# circuitDiagram.net
KiCad netlist of a schematic drawn in EAGLE
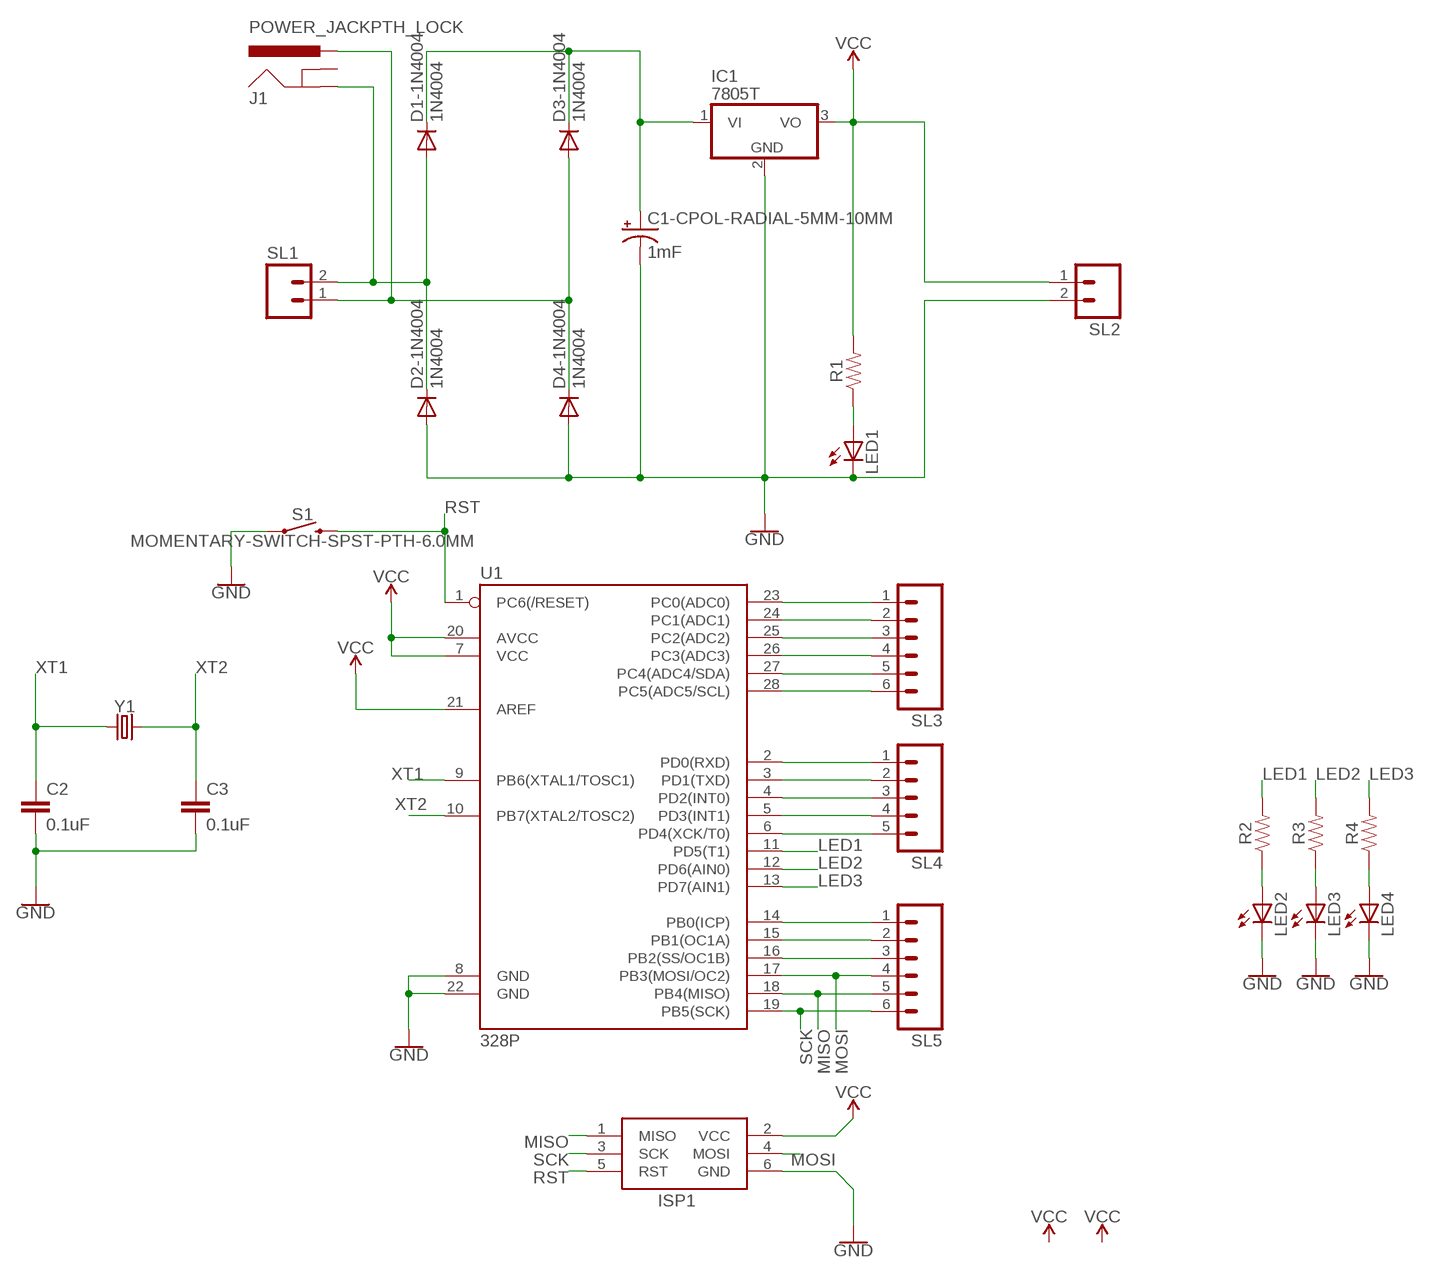
[diagram p0: schematic, sheet 1]

(export (version "E")
  (design (tool "Eeschema 10.0.6"))
  (components
    (comp (ref "C1-CPOL-RADIAL-5MM-10MM")
      (value "1mF")
      (footprint "eagle-import:CPOL-RADIAL-5MM-10MM")
      (libsource (lib "eagle-import") (part "1000UF-RADIAL-5MM-25V-20%"))
    )
    (comp (ref "C2")
      (value "0.1uF")
      (footprint "eagle-import:CAP-PTH-SMALL-KIT")
      (libsource (lib "eagle-import") (part "0.1UF-KIT-EZ-50V-20%"))
    )
    (comp (ref "C3")
      (value "0.1uF")
      (footprint "eagle-import:CAP-PTH-SMALL-KIT")
      (libsource (lib "eagle-import") (part "0.1UF-KIT-EZ-50V-20%"))
    )
    (comp (ref "D1-1N4004")
      (value "1N4004")
      (footprint "eagle-import:DO41-10")
      (libsource (lib "eagle-import") (part "1N4004"))
    )
    (comp (ref "D2-1N4004")
      (value "1N4004")
      (footprint "eagle-import:DO41-10")
      (libsource (lib "eagle-import") (part "1N4004"))
    )
    (comp (ref "D3-1N4004")
      (value "1N4004")
      (footprint "eagle-import:DO41-10")
      (libsource (lib "eagle-import") (part "1N4004"))
    )
    (comp (ref "D4-1N4004")
      (value "1N4004")
      (footprint "eagle-import:DO41-10")
      (libsource (lib "eagle-import") (part "1N4004"))
    )
    (comp (ref "IC1")
      (value "7805T")
      (footprint "eagle-import:TO220H")
      (libsource (lib "eagle-import") (part "78T05"))
    )
    (comp (ref "ISP1")
      (value "AVRISP-6")
      (footprint "eagle-import:AVRISP")
      (libsource (lib "eagle-import") (part "AVRISP-6"))
    )
    (comp (ref "J1")
      (value "POWER_JACKPTH_LOCK")
      (footprint "eagle-import:POWER_JACK_PTH_LOCK")
      (libsource (lib "eagle-import") (part "POWER_JACKPTH_LOCK"))
    )
    (comp (ref "LED1")
      (value "LED3MM")
      (footprint "eagle-import:LED3MM")
      (libsource (lib "eagle-import") (part "LED3MM"))
    )
    (comp (ref "LED2")
      (value "LED3MM")
      (footprint "eagle-import:LED3MM")
      (libsource (lib "eagle-import") (part "LED3MM"))
    )
    (comp (ref "LED3")
      (value "LED3MM")
      (footprint "eagle-import:LED3MM")
      (libsource (lib "eagle-import") (part "LED3MM"))
    )
    (comp (ref "LED4")
      (value "LED3MM")
      (footprint "eagle-import:LED3MM")
      (libsource (lib "eagle-import") (part "LED3MM"))
    )
    (comp (ref "R1")
      (value "RESISTORAXIAL-0.3")
      (footprint "eagle-import:AXIAL-0.3")
      (libsource (lib "eagle-import") (part "RESISTORAXIAL-0.3"))
    )
    (comp (ref "R2")
      (value "RESISTORAXIAL-0.3")
      (footprint "eagle-import:AXIAL-0.3")
      (libsource (lib "eagle-import") (part "RESISTORAXIAL-0.3"))
    )
    (comp (ref "R3")
      (value "RESISTORAXIAL-0.3")
      (footprint "eagle-import:AXIAL-0.3")
      (libsource (lib "eagle-import") (part "RESISTORAXIAL-0.3"))
    )
    (comp (ref "R4")
      (value "RESISTORAXIAL-0.3")
      (footprint "eagle-import:AXIAL-0.3")
      (libsource (lib "eagle-import") (part "RESISTORAXIAL-0.3"))
    )
    (comp (ref "S1")
      (value "MOMENTARY-SWITCH-SPST-PTH-6.0MM")
      (footprint "eagle-import:TACTILE_SWITCH_PTH_6.0MM")
      (libsource (lib "eagle-import") (part "MOMENTARY-SWITCH-SPST-PTH-6.0MM"))
    )
    (comp (ref "SL1")
      (value "M02")
      (footprint "eagle-import:02P")
      (libsource (lib "eagle-import") (part "M02"))
    )
    (comp (ref "SL2")
      (value "M02")
      (footprint "eagle-import:02P")
      (libsource (lib "eagle-import") (part "M02"))
    )
    (comp (ref "SL3")
      (value "M06")
      (footprint "eagle-import:06P")
      (libsource (lib "eagle-import") (part "M06"))
    )
    (comp (ref "SL4")
      (value "M05")
      (footprint "eagle-import:05P")
      (libsource (lib "eagle-import") (part "M05"))
    )
    (comp (ref "SL5")
      (value "M06")
      (footprint "eagle-import:06P")
      (libsource (lib "eagle-import") (part "M06"))
    )
    (comp (ref "U1")
      (value "328P")
      (footprint "eagle-import:DIP28")
      (libsource (lib "eagle-import") (part "ATMEGA328P_PDIP"))
    )
    (comp (ref "Y1")
      (value "CRYSTALPTH-HC49US")
      (footprint "eagle-import:HC49US")
      (libsource (lib "eagle-import") (part "CRYSTALPTH-HC49US"))
    )
  )
  (nets
    (net (code "1") (name "/LED1") (class "Default")
      (node (ref "R2") (pin "P$2") (pinfunction "2_P$2") (pintype "passive"))
      (node (ref "U1") (pin "11") (pinfunction "PD5(T1)_11") (pintype "bidirectional"))
    )
    (net (code "2") (name "/LED2") (class "Default")
      (node (ref "R3") (pin "P$2") (pinfunction "2_P$2") (pintype "passive"))
      (node (ref "U1") (pin "12") (pinfunction "PD6(AIN0)_12") (pintype "bidirectional"))
    )
    (net (code "3") (name "/LED3") (class "Default")
      (node (ref "R4") (pin "P$2") (pinfunction "2_P$2") (pintype "passive"))
      (node (ref "U1") (pin "13") (pinfunction "PD7(AIN1)_13") (pintype "bidirectional"))
    )
    (net (code "4") (name "/MISO") (class "Default")
      (node (ref "ISP1") (pin "1") (pinfunction "MISO_1") (pintype "input"))
      (node (ref "SL5") (pin "5") (pinfunction "5_5") (pintype "passive"))
      (node (ref "U1") (pin "18") (pinfunction "PB4(MISO)_18") (pintype "bidirectional"))
    )
    (net (code "5") (name "/MOSI") (class "Default")
      (node (ref "ISP1") (pin "4") (pinfunction "MOSI_4") (pintype "output"))
      (node (ref "SL5") (pin "4") (pinfunction "4_4") (pintype "passive"))
      (node (ref "U1") (pin "17") (pinfunction "PB3(MOSI/OC2)_17") (pintype "bidirectional"))
    )
    (net (code "6") (name "/RST") (class "Default")
      (node (ref "ISP1") (pin "5") (pinfunction "RST_5") (pintype "output"))
      (node (ref "S1") (pin "3") (pinfunction "2_3") (pintype "passive"))
      (node (ref "U1") (pin "1") (pinfunction "PC6(/RESET)_1") (pintype "bidirectional"))
    )
    (net (code "7") (name "/SCK") (class "Default")
      (node (ref "ISP1") (pin "3") (pinfunction "SCK_3") (pintype "output"))
      (node (ref "SL5") (pin "6") (pinfunction "6_6") (pintype "passive"))
      (node (ref "U1") (pin "19") (pinfunction "PB5(SCK)_19") (pintype "bidirectional"))
    )
    (net (code "8") (name "/XT1") (class "Default")
      (node (ref "C2") (pin "1") (pinfunction "1_1") (pintype "passive"))
      (node (ref "U1") (pin "9") (pinfunction "PB6(XTAL1/TOSC1)_9") (pintype "bidirectional"))
      (node (ref "Y1") (pin "1") (pinfunction "1_1") (pintype "passive"))
    )
    (net (code "9") (name "/XT2") (class "Default")
      (node (ref "C3") (pin "1") (pinfunction "1_1") (pintype "passive"))
      (node (ref "U1") (pin "10") (pinfunction "PB7(XTAL2/TOSC2)_10") (pintype "bidirectional"))
      (node (ref "Y1") (pin "2") (pinfunction "2_2") (pintype "passive"))
    )
    (net (code "10") (name "GND") (class "Default")
      (node (ref "C1-CPOL-RADIAL-5MM-10MM") (pin "-") (pinfunction "-_-") (pintype "passive"))
      (node (ref "C2") (pin "2") (pinfunction "2_2") (pintype "passive"))
      (node (ref "C3") (pin "2") (pinfunction "2_2") (pintype "passive"))
      (node (ref "D2-1N4004") (pin "A") (pinfunction "A_A") (pintype "passive"))
      (node (ref "D4-1N4004") (pin "A") (pinfunction "A_A") (pintype "passive"))
      (node (ref "IC1") (pin "2") (pinfunction "GND_2") (pintype "passive"))
      (node (ref "ISP1") (pin "6") (pinfunction "GND_6") (pintype "power_in"))
      (node (ref "LED1") (pin "K") (pinfunction "C_K") (pintype "passive"))
      (node (ref "LED2") (pin "K") (pinfunction "C_K") (pintype "passive"))
      (node (ref "LED3") (pin "K") (pinfunction "C_K") (pintype "passive"))
      (node (ref "LED4") (pin "K") (pinfunction "C_K") (pintype "passive"))
      (node (ref "S1") (pin "1") (pinfunction "1_1") (pintype "passive"))
      (node (ref "SL2") (pin "2") (pinfunction "2_2") (pintype "passive"))
      (node (ref "U1") (pin "22") (pinfunction "GND_22") (pintype "bidirectional"))
      (node (ref "U1") (pin "8") (pinfunction "GND_8") (pintype "bidirectional"))
    )
    (net (code "11") (name "Net-(D1-1N4004-PadA)") (class "Default")
      (node (ref "D1-1N4004") (pin "A") (pinfunction "A_A") (pintype "passive"))
      (node (ref "D2-1N4004") (pin "C") (pinfunction "C_C") (pintype "passive"))
      (node (ref "J1") (pin "GND") (pinfunction "GND_GND") (pintype "bidirectional"))
      (node (ref "SL1") (pin "2") (pinfunction "2_2") (pintype "passive"))
    )
    (net (code "12") (name "Net-(D3-1N4004-PadA)") (class "Default")
      (node (ref "D3-1N4004") (pin "A") (pinfunction "A_A") (pintype "passive"))
      (node (ref "D4-1N4004") (pin "C") (pinfunction "C_C") (pintype "passive"))
      (node (ref "J1") (pin "PWR") (pinfunction "PWR_PWR") (pintype "bidirectional"))
      (node (ref "SL1") (pin "1") (pinfunction "1_1") (pintype "passive"))
    )
    (net (code "13") (name "Net-(IC1-VI)") (class "Default")
      (node (ref "C1-CPOL-RADIAL-5MM-10MM") (pin "+") (pinfunction "+_+") (pintype "passive"))
      (node (ref "D1-1N4004") (pin "C") (pinfunction "C_C") (pintype "passive"))
      (node (ref "D3-1N4004") (pin "C") (pinfunction "C_C") (pintype "passive"))
      (node (ref "IC1") (pin "1") (pinfunction "VI_1") (pintype "input"))
    )
    (net (code "14") (name "Net-(R1-1)") (class "Default")
      (node (ref "LED1") (pin "A") (pinfunction "A_A") (pintype "passive"))
      (node (ref "R1") (pin "P$1") (pinfunction "1_P$1") (pintype "passive"))
    )
    (net (code "15") (name "Net-(R2-1)") (class "Default")
      (node (ref "LED2") (pin "A") (pinfunction "A_A") (pintype "passive"))
      (node (ref "R2") (pin "P$1") (pinfunction "1_P$1") (pintype "passive"))
    )
    (net (code "16") (name "Net-(R3-1)") (class "Default")
      (node (ref "LED3") (pin "A") (pinfunction "A_A") (pintype "passive"))
      (node (ref "R3") (pin "P$1") (pinfunction "1_P$1") (pintype "passive"))
    )
    (net (code "17") (name "Net-(R4-1)") (class "Default")
      (node (ref "LED4") (pin "A") (pinfunction "A_A") (pintype "passive"))
      (node (ref "R4") (pin "P$1") (pinfunction "1_P$1") (pintype "passive"))
    )
    (net (code "18") (name "Net-(U1-PB0(ICP))") (class "Default")
      (node (ref "SL5") (pin "1") (pinfunction "1_1") (pintype "passive"))
      (node (ref "U1") (pin "14") (pinfunction "PB0(ICP)_14") (pintype "bidirectional"))
    )
    (net (code "19") (name "Net-(U1-PB1(OC1A))") (class "Default")
      (node (ref "SL5") (pin "2") (pinfunction "2_2") (pintype "passive"))
      (node (ref "U1") (pin "15") (pinfunction "PB1(OC1A)_15") (pintype "bidirectional"))
    )
    (net (code "20") (name "Net-(U1-PB2(SS{slash}OC1B))") (class "Default")
      (node (ref "SL5") (pin "3") (pinfunction "3_3") (pintype "passive"))
      (node (ref "U1") (pin "16") (pinfunction "PB2(SS/OC1B)_16") (pintype "bidirectional"))
    )
    (net (code "21") (name "Net-(U1-PC0(ADC0))") (class "Default")
      (node (ref "SL3") (pin "1") (pinfunction "1_1") (pintype "passive"))
      (node (ref "U1") (pin "23") (pinfunction "PC0(ADC0)_23") (pintype "bidirectional"))
    )
    (net (code "22") (name "Net-(U1-PC1(ADC1))") (class "Default")
      (node (ref "SL3") (pin "2") (pinfunction "2_2") (pintype "passive"))
      (node (ref "U1") (pin "24") (pinfunction "PC1(ADC1)_24") (pintype "bidirectional"))
    )
    (net (code "23") (name "Net-(U1-PC2(ADC2))") (class "Default")
      (node (ref "SL3") (pin "3") (pinfunction "3_3") (pintype "passive"))
      (node (ref "U1") (pin "25") (pinfunction "PC2(ADC2)_25") (pintype "bidirectional"))
    )
    (net (code "24") (name "Net-(U1-PC3(ADC3))") (class "Default")
      (node (ref "SL3") (pin "4") (pinfunction "4_4") (pintype "passive"))
      (node (ref "U1") (pin "26") (pinfunction "PC3(ADC3)_26") (pintype "bidirectional"))
    )
    (net (code "25") (name "Net-(U1-PC4(ADC4{slash}SDA))") (class "Default")
      (node (ref "SL3") (pin "5") (pinfunction "5_5") (pintype "passive"))
      (node (ref "U1") (pin "27") (pinfunction "PC4(ADC4/SDA)_27") (pintype "bidirectional"))
    )
    (net (code "26") (name "Net-(U1-PC5(ADC5{slash}SCL))") (class "Default")
      (node (ref "SL3") (pin "6") (pinfunction "6_6") (pintype "passive"))
      (node (ref "U1") (pin "28") (pinfunction "PC5(ADC5/SCL)_28") (pintype "bidirectional"))
    )
    (net (code "27") (name "Net-(U1-PD0(RXD))") (class "Default")
      (node (ref "SL4") (pin "1") (pinfunction "1_1") (pintype "passive"))
      (node (ref "U1") (pin "2") (pinfunction "PD0(RXD)_2") (pintype "bidirectional"))
    )
    (net (code "28") (name "Net-(U1-PD1(TXD))") (class "Default")
      (node (ref "SL4") (pin "2") (pinfunction "2_2") (pintype "passive"))
      (node (ref "U1") (pin "3") (pinfunction "PD1(TXD)_3") (pintype "bidirectional"))
    )
    (net (code "29") (name "Net-(U1-PD2(INT0))") (class "Default")
      (node (ref "SL4") (pin "3") (pinfunction "3_3") (pintype "passive"))
      (node (ref "U1") (pin "4") (pinfunction "PD2(INT0)_4") (pintype "bidirectional"))
    )
    (net (code "30") (name "Net-(U1-PD3(INT1))") (class "Default")
      (node (ref "SL4") (pin "4") (pinfunction "4_4") (pintype "passive"))
      (node (ref "U1") (pin "5") (pinfunction "PD3(INT1)_5") (pintype "bidirectional"))
    )
    (net (code "31") (name "Net-(U1-PD4(XCK{slash}T0))") (class "Default")
      (node (ref "SL4") (pin "5") (pinfunction "5_5") (pintype "passive"))
      (node (ref "U1") (pin "6") (pinfunction "PD4(XCK/T0)_6") (pintype "bidirectional"))
    )
    (net (code "32") (name "VCC") (class "Default")
      (node (ref "IC1") (pin "3") (pinfunction "VO_3") (pintype "passive"))
      (node (ref "ISP1") (pin "2") (pinfunction "VCC_2") (pintype "power_in"))
      (node (ref "R1") (pin "P$2") (pinfunction "2_P$2") (pintype "passive"))
      (node (ref "SL2") (pin "1") (pinfunction "1_1") (pintype "passive"))
      (node (ref "U1") (pin "20") (pinfunction "AVCC_20") (pintype "bidirectional"))
      (node (ref "U1") (pin "21") (pinfunction "AREF_21") (pintype "bidirectional"))
      (node (ref "U1") (pin "7") (pinfunction "VCC_7") (pintype "bidirectional"))
    )
    (net (code "33") (name "unconnected-(J1-PadGNDBREAK)") (class "Default")
      (node (ref "J1") (pin "GNDBREAK") (pinfunction "GNDBREAK_GNDBREAK") (pintype "bidirectional"))
    )
  )
)
